# afstandbediening_shematic.net
KiCad netlist of a schematic drawn in Altium Designer
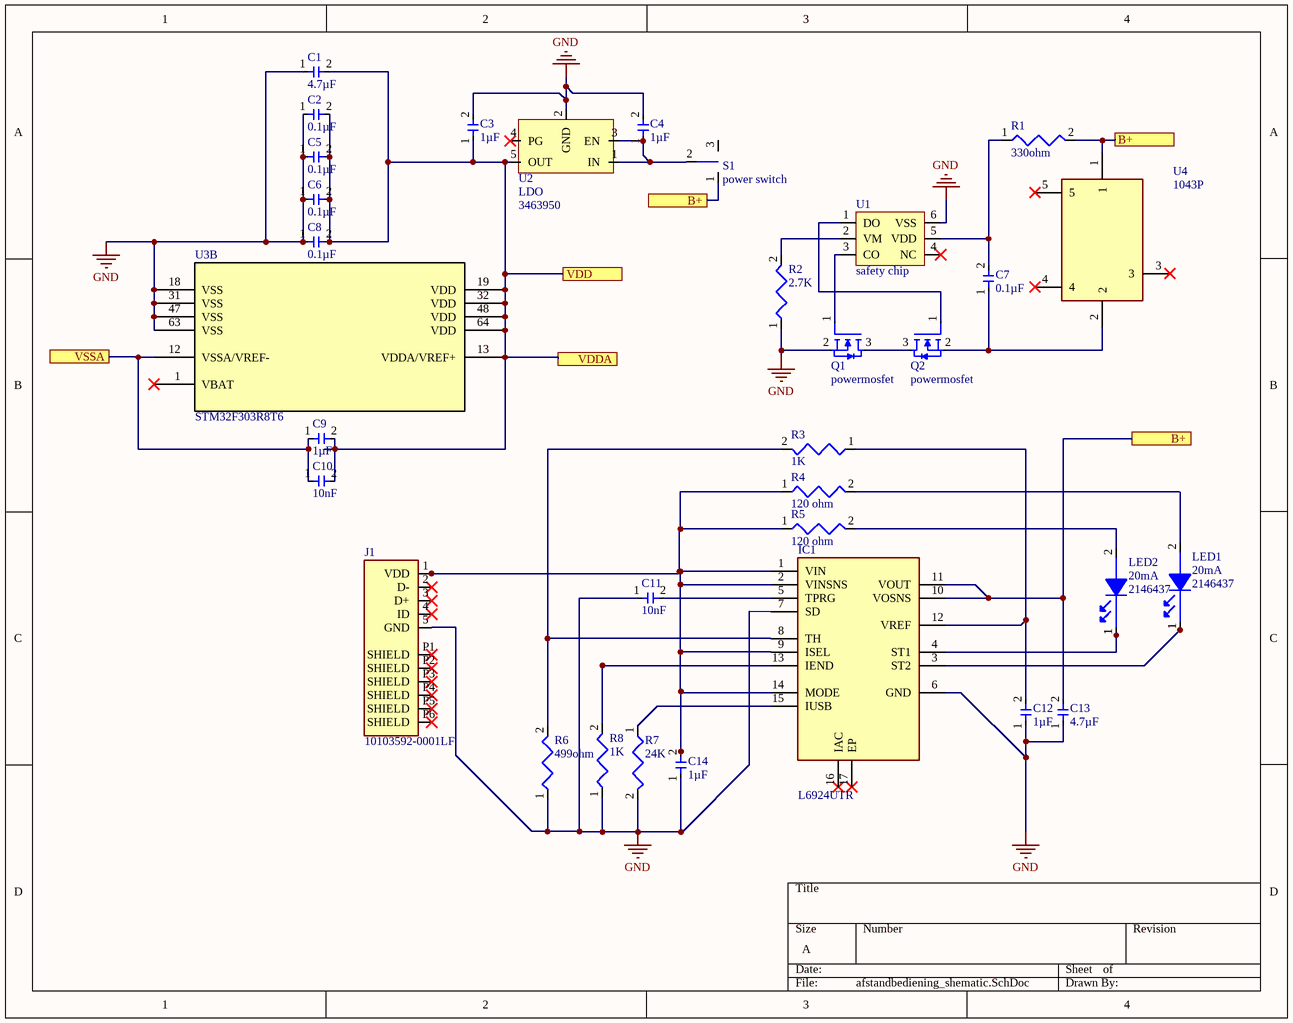
[diagram p0: afstandbediening_shematic.SchDoc]

(export (version "E")
  (design (tool "Eeschema 10.0.6"))
  (components
    (comp (ref "C1")
      (value "4.7µF")
      (footprint "0603")
      (fields
        (field (name "MANUFACTURER") "Kyocera AVX")
        (field (name "MANUFACTURER PART NUMBER") "0603ZD475KAT2A")
        (field (name "TOLERANCE") "10%")
      )
      (libsource (lib "afstandsbediening_library") (part "0603ZD475KAT2A"))
    )
    (comp (ref "C2")
      (value "0.1µF")
      (footprint "0603")
      (description "Cap Ceramic 0.1uF 16V X7R 10% SMD 0603 125C Paper T/R")
      (fields
        (field (name "MANUFACTURER") "Kyocera AVX")
        (field (name "MANUFACTURER PART NUMBER") "0603YC104KAT2A")
      )
      (libsource (lib "afstandsbediening_library") (part "0603YC104KAT2A"))
    )
    (comp (ref "C3")
      (value "1µF")
      (footprint "0603")
      (fields
        (field (name "MANUFACTURER") "Kyocera AVX")
        (field (name "MANUFACTURER PART NUMBER") "0603YD105KAT2A")
        (field (name "TOLERANCE") "10%")
      )
      (libsource (lib "afstandsbediening_library") (part "0603YD105KAT2A"))
    )
    (comp (ref "C4")
      (value "1µF")
      (footprint "0603")
      (fields
        (field (name "MANUFACTURER") "Kyocera AVX")
        (field (name "MANUFACTURER PART NUMBER") "0603YD105KAT2A")
        (field (name "TOLERANCE") "10%")
      )
      (libsource (lib "afstandsbediening_library") (part "0603YD105KAT2A"))
    )
    (comp (ref "C5")
      (value "0.1µF")
      (footprint "0603")
      (description "Cap Ceramic 0.1uF 16V X7R 10% SMD 0603 125C Paper T/R")
      (fields
        (field (name "MANUFACTURER") "Kyocera AVX")
        (field (name "MANUFACTURER PART NUMBER") "0603YC104KAT2A")
      )
      (libsource (lib "afstandsbediening_library") (part "0603YC104KAT2A"))
    )
    (comp (ref "C6")
      (value "0.1µF")
      (footprint "0603")
      (description "Cap Ceramic 0.1uF 16V X7R 10% SMD 0603 125C Paper T/R")
      (fields
        (field (name "MANUFACTURER") "Kyocera AVX")
        (field (name "MANUFACTURER PART NUMBER") "0603YC104KAT2A")
      )
      (libsource (lib "afstandsbediening_library") (part "0603YC104KAT2A"))
    )
    (comp (ref "C7")
      (value "0.1µF")
      (footprint "0603")
      (description "Cap Ceramic 0.1uF 16V X7R 10% SMD 0603 125C Paper T/R")
      (fields
        (field (name "MANUFACTURER") "Kyocera AVX")
        (field (name "MANUFACTURER PART NUMBER") "0603YC104KAT2A")
      )
      (libsource (lib "afstandsbediening_library") (part "0603YC104KAT2A"))
    )
    (comp (ref "C8")
      (value "0.1µF")
      (footprint "0603")
      (description "Cap Ceramic 0.1uF 16V X7R 10% SMD 0603 125C Paper T/R")
      (fields
        (field (name "MANUFACTURER") "Kyocera AVX")
        (field (name "MANUFACTURER PART NUMBER") "0603YC104KAT2A")
      )
      (libsource (lib "afstandsbediening_library") (part "0603YC104KAT2A"))
    )
    (comp (ref "C9")
      (value "1µF")
      (footprint "0603")
      (fields
        (field (name "MANUFACTURER") "Kyocera AVX")
        (field (name "MANUFACTURER PART NUMBER") "0603YD105KAT2A")
        (field (name "TOLERANCE") "10%")
      )
      (libsource (lib "afstandsbediening_library") (part "0603YD105KAT2A"))
    )
    (comp (ref "C10")
      (value "10nF")
      (footprint "0603")
      (fields
        (field (name "MANUFACTURER") "Kyocera AVX")
        (field (name "MANUFACTURER PART NUMBER") "0603YC103KAT2A")
        (field (name "TOLERANCE") "10%")
      )
      (libsource (lib "afstandsbediening_library") (part "0603YC103KAT2A"))
    )
    (comp (ref "C11")
      (value "10nF")
      (footprint "0603")
      (fields
        (field (name "MANUFACTURER") "Kyocera AVX")
        (field (name "MANUFACTURER PART NUMBER") "0603YC103KAT2A")
        (field (name "TOLERANCE") "10%")
      )
      (libsource (lib "afstandsbediening_library") (part "0603YC103KAT2A"))
    )
    (comp (ref "C12")
      (value "1µF")
      (footprint "0603")
      (fields
        (field (name "MANUFACTURER") "Kyocera AVX")
        (field (name "MANUFACTURER PART NUMBER") "0603YD105KAT2A")
        (field (name "TOLERANCE") "10%")
      )
      (libsource (lib "afstandsbediening_library") (part "0603YD105KAT2A"))
    )
    (comp (ref "C13")
      (value "4.7µF")
      (footprint "0603")
      (fields
        (field (name "MANUFACTURER") "Kyocera AVX")
        (field (name "MANUFACTURER PART NUMBER") "0603ZD475KAT2A")
        (field (name "TOLERANCE") "10%")
      )
      (libsource (lib "afstandsbediening_library") (part "0603ZD475KAT2A"))
    )
    (comp (ref "C14")
      (value "1µF")
      (footprint "0603")
      (fields
        (field (name "MANUFACTURER") "Kyocera AVX")
        (field (name "MANUFACTURER PART NUMBER") "0603YD105KAT2A")
        (field (name "TOLERANCE") "10%")
      )
      (libsource (lib "afstandsbediening_library") (part "0603YD105KAT2A"))
    )
    (comp (ref "IC1")
      (value "L6924UTR")
      (footprint "SamacSys:QFN50P300X300X100-17N-D")
      (description "Integrated Circuit")
      (fields (field (name "MOUSER2 PART NUMBER") "511-L6924UTR"))
      (libsource (lib "SamacSys") (part "L6924UTR"))
    )
    (comp (ref "J1")
      (value "10103592-0001LF")
      (footprint "AMPHENOL_10103592-0001LF")
      (description "USB - micro B USB 2.0 Receptacle Connector 5 Position Surface Mount, Right Angle; Through Hole")
      (fields (field (name "MF") "Amphenol ICC"))
      (libsource (lib "SamacSys") (part "10103592-0001LF"))
    )
    (comp (ref "LED1")
      (value "20mA")
      (footprint "KP-1608QBC-D")
      (description "LED Uni-Color Blue 468nm 2-Pin Chip LED T/R")
      (fields
        (field (name "MANUFACTURER") "Kingbright")
        (field (name "MANUFACTURER PART NUMBER") "KP-1608QBC-D")
        (field (name "SUPPLIER PART NUMBER 1") "2146437")
      )
      (libsource (lib "afstandsbediening_library") (part "KP-1608QBC-D"))
    )
    (comp (ref "LED2")
      (value "20mA")
      (footprint "KP-1608QBC-D")
      (description "LED Uni-Color Blue 468nm 2-Pin Chip LED T/R")
      (fields
        (field (name "MANUFACTURER") "Kingbright")
        (field (name "MANUFACTURER PART NUMBER") "KP-1608QBC-D")
        (field (name "SUPPLIER PART NUMBER 1") "2146437")
      )
      (libsource (lib "afstandsbediening_library") (part "KP-1608QBC-D"))
    )
    (comp (ref "Q1")
      (value "powermosfet")
      (footprint "SI2336DS-T1-GE3 - duplicate")
      (description "MOSFET N-CH 30V 5.2A SOT-23")
      (fields
        (field (name "MANUFACTURER") "Vishay Siliconix")
        (field (name "MANUFACTURER PART NUMBER") "SI2336DS-T1-GE3")
      )
      (libsource (lib "afstandsbediening_library") (part "SI2336DS-T1-GE3"))
    )
    (comp (ref "Q2")
      (value "powermosfet")
      (footprint "SI2336DS-T1-GE3 - duplicate")
      (description "MOSFET N-CH 30V 5.2A SOT-23")
      (fields
        (field (name "MANUFACTURER") "Vishay Siliconix")
        (field (name "MANUFACTURER PART NUMBER") "SI2336DS-T1-GE3")
      )
      (libsource (lib "afstandsbediening_library") (part "SI2336DS-T1-GE3"))
    )
    (comp (ref "R1")
      (value "330ohm")
      (footprint "MCWR08 - duplicate")
      (fields
        (field (name "MANUFACTURER") "Multicomp")
        (field (name "MANUFACTURER PART NUMBER") "MCWR08X3300FTL")
        (field (name "TOLERANCE") "1%")
      )
      (libsource (lib "afstandsbediening_library") (part "MCWR08X3300FTL"))
    )
    (comp (ref "R2")
      (value "2.7K")
      (footprint "CRCW0603")
      (description "SMD Resistor, Thick film 2.7 kOhm,  ±  1 %, 0603, CRCW06032K70FKEA, Vishay")
      (fields
        (field (name "MANUFACTURER") "Vishay")
        (field (name "MANUFACTURER PART NUMBER") "CRCW06032K70FKEA")
      )
      (libsource (lib "afstandsbediening_library") (part "CRCW06032K70FKEA"))
    )
    (comp (ref "R3")
      (value "1K")
      (footprint "CRCW0603")
      (fields
        (field (name "MANUFACTURER") "Vishay Dale")
        (field (name "MANUFACTURER PART NUMBER") "CRCW06031K00JNEA")
        (field (name "TOLERANCE") "5%")
      )
      (libsource (lib "afstandsbediening_library") (part "CRCW06031K00JNEA"))
    )
    (comp (ref "R4")
      (value "120 ohm")
      (footprint "CRCW0603")
      (description "Res Thick Film 0603 120 Ohm 1% 1/10W ±100ppm/°C Molded SMD Paper T/R")
      (fields
        (field (name "MANUFACTURER") "Vishay")
        (field (name "MANUFACTURER PART NUMBER") "CRCW0603120RFKEA")
      )
      (libsource (lib "afstandsbediening_library") (part "CRCW0603120RFKEA"))
    )
    (comp (ref "R5")
      (value "120 ohm")
      (footprint "CRCW0603")
      (description "Res Thick Film 0603 120 Ohm 1% 1/10W ±100ppm/°C Molded SMD Paper T/R")
      (fields
        (field (name "MANUFACTURER") "Vishay")
        (field (name "MANUFACTURER PART NUMBER") "CRCW0603120RFKEA")
      )
      (libsource (lib "afstandsbediening_library") (part "CRCW0603120RFKEA"))
    )
    (comp (ref "R6")
      (value "499ohm")
      (footprint "MCWR06")
      (description "Res, 499R, 1%, 0.1W, 0603, Thick Film")
      (fields
        (field (name "MANUFACTURER") "Multicomp")
        (field (name "MANUFACTURER PART NUMBER") "MCWR06X4990FTL")
      )
      (libsource (lib "afstandsbediening_library") (part "MCWR06X4990FTL"))
    )
    (comp (ref "R7")
      (value "24K")
      (footprint "MCWR06")
      (description "MULTICOMP - MCWR06X2402FTL - RES, 24K, 1%, 0.1W, THICK FILM")
      (fields
        (field (name "MANUFACTURER") "Multicomp")
        (field (name "MANUFACTURER PART NUMBER") "MCWR06X2402FTL")
      )
      (libsource (lib "afstandsbediening_library") (part "MCWR06X2402FTL"))
    )
    (comp (ref "R8")
      (value "1K")
      (footprint "CRCW0603")
      (fields
        (field (name "MANUFACTURER") "Vishay Dale")
        (field (name "MANUFACTURER PART NUMBER") "CRCW06031K00JNEA")
        (field (name "TOLERANCE") "5%")
      )
      (libsource (lib "afstandsbediening_library") (part "CRCW06031K00JNEA"))
    )
    (comp (ref "S1")
      (value "power switch")
      (footprint "T101MH9ABE")
      (description "SWITCH TOGGLE SPDT 0.4VA 20V")
      (fields (field (name "MANUFACTURER") "ITT C&K") (field (name "MANUFACTURER PART NUMBER") "T101MH9ABE"))
      (libsource (lib "afstandsbediening_library") (part "T101MH9ABE"))
    )
    (comp (ref "U1")
      (value "safety chip")
      (footprint "AP9101CK6-AETRG1")
      (description "IC BATT PROT LI-ION 1-CELL SOT26")
      (fields
        (field (name "MANUFACTURER") "Diodes")
        (field (name "MANUFACTURER PART NUMBER") "AP9101CK6-AETRG1")
      )
      (libsource (lib "afstandsbediening_library") (part "AP9101CK6-AETRG1"))
    )
    (comp (ref "U2")
      (value "LDO")
      (footprint "NCP164C")
      (description "MAX 5V, MIN 1.6V OUTPUT 3V")
      (fields
        (field (name "MANUFACTURER") "ON Semiconductor")
        (field (name "MANUFACTURER PART NUMBER") "NCP164CSN300T1G")
        (field (name "SUPPLIER PART NUMBER 1") "3463950")
      )
      (libsource (lib "afstandsbediening_library") (part "NCP164CSN300T1G"))
    )
    (comp (ref "U3")
      (value "STM32F303R8T6")
      (footprint "LQFP64-10x10mm")
      (description "No Description Available")
      (fields (field (name "COPYRIGHT") "Copyright (C) 2018 Accelerated Designs. All rights reserved"))
      (libsource (lib "2021-02-22_19-54-40") (part "STM32F303R8T6"))
    )
    (comp (ref "U4")
      (value "1043P")
      (footprint "SamacSys:1043P")
      (description "Undefined or Miscellaneous")
      (libsource (lib "SamacSys") (part "1043P"))
    )
  )
  (nets
    (net (code "1") (name "/B+") (class "Default")
      (node (ref "C13") (pin "2") (pinfunction "18_2") (pintype "passive"))
      (node (ref "IC1") (pin "10") (pinfunction "VOSNS_10") (pintype "passive"))
      (node (ref "IC1") (pin "11") (pinfunction "VOUT_11") (pintype "passive"))
      (node (ref "R1") (pin "2") (pinfunction "2_2") (pintype "passive"))
      (node (ref "S1") (pin "1") (pinfunction "1_1") (pintype "passive"))
      (node (ref "U4") (pin "1") (pinfunction "1_1") (pintype "passive"))
    )
    (net (code "2") (name "/VDD") (class "Default")
      (node (ref "C1") (pin "2") (pinfunction "18_2") (pintype "passive"))
      (node (ref "C10") (pin "2") (pinfunction "18_2") (pintype "passive"))
      (node (ref "C2") (pin "2") (pinfunction "18_2") (pintype "passive"))
      (node (ref "C3") (pin "1") (pinfunction "1_1") (pintype "passive"))
      (node (ref "C5") (pin "2") (pinfunction "18_2") (pintype "passive"))
      (node (ref "C6") (pin "2") (pinfunction "18_2") (pintype "passive"))
      (node (ref "C8") (pin "2") (pinfunction "18_2") (pintype "passive"))
      (node (ref "C9") (pin "2") (pinfunction "18_2") (pintype "passive"))
      (node (ref "U2") (pin "5") (pinfunction "OUT_5") (pintype "passive"))
      (node (ref "U3") (pin "13") (pinfunction "VDDA/VREF+_13") (pintype "power_in"))
      (node (ref "U3") (pin "19") (pinfunction "VDD_19") (pintype "power_in"))
      (node (ref "U3") (pin "32") (pinfunction "VDD_32") (pintype "power_in"))
      (node (ref "U3") (pin "48") (pinfunction "VDD_48") (pintype "power_in"))
      (node (ref "U3") (pin "64") (pinfunction "VDD_64") (pintype "power_in"))
    )
    (net (code "3") (name "/VSSA") (class "Default")
      (node (ref "C10") (pin "1") (pinfunction "1_1") (pintype "passive"))
      (node (ref "C9") (pin "1") (pinfunction "1_1") (pintype "passive"))
      (node (ref "U3") (pin "12") (pinfunction "VSSA/VREF-_12") (pintype "power_in"))
    )
    (net (code "4") (name "GND") (class "Default")
      (node (ref "C1") (pin "1") (pinfunction "1_1") (pintype "passive"))
      (node (ref "C11") (pin "1") (pinfunction "1_1") (pintype "passive"))
      (node (ref "C12") (pin "1") (pinfunction "1_1") (pintype "passive"))
      (node (ref "C13") (pin "1") (pinfunction "1_1") (pintype "passive"))
      (node (ref "C14") (pin "1") (pinfunction "1_1") (pintype "passive"))
      (node (ref "C2") (pin "1") (pinfunction "1_1") (pintype "passive"))
      (node (ref "C3") (pin "2") (pinfunction "18_2") (pintype "passive"))
      (node (ref "C4") (pin "2") (pinfunction "18_2") (pintype "passive"))
      (node (ref "C5") (pin "1") (pinfunction "1_1") (pintype "passive"))
      (node (ref "C6") (pin "1") (pinfunction "1_1") (pintype "passive"))
      (node (ref "C8") (pin "1") (pinfunction "1_1") (pintype "passive"))
      (node (ref "IC1") (pin "6") (pinfunction "GND_6") (pintype "passive"))
      (node (ref "IC1") (pin "7") (pinfunction "SD_7") (pintype "passive"))
      (node (ref "J1") (pin "5") (pinfunction "GND_5") (pintype "power_in"))
      (node (ref "Q1") (pin "2") (pinfunction "S_2") (pintype "passive"))
      (node (ref "R2") (pin "1") (pinfunction "1_1") (pintype "passive"))
      (node (ref "R6") (pin "1") (pinfunction "1_1") (pintype "passive"))
      (node (ref "R7") (pin "2") (pinfunction "2_2") (pintype "passive"))
      (node (ref "R8") (pin "1") (pinfunction "1_1") (pintype "passive"))
      (node (ref "U1") (pin "6") (pinfunction "VSS_6") (pintype "passive"))
      (node (ref "U2") (pin "2") (pinfunction "GND_2") (pintype "passive"))
      (node (ref "U3") (pin "18") (pinfunction "VSS_18") (pintype "power_in"))
      (node (ref "U3") (pin "31") (pinfunction "VSS_31") (pintype "power_in"))
      (node (ref "U3") (pin "47") (pinfunction "VSS_47") (pintype "power_in"))
      (node (ref "U3") (pin "63") (pinfunction "VSS_63") (pintype "power_in"))
    )
    (net (code "5") (name "Net-(C7-18)") (class "Default")
      (node (ref "C7") (pin "2") (pinfunction "18_2") (pintype "passive"))
      (node (ref "R1") (pin "1") (pinfunction "1_1") (pintype "passive"))
      (node (ref "U1") (pin "5") (pinfunction "VDD_5") (pintype "passive"))
    )
    (net (code "6") (name "Net-(C11-18)") (class "Default")
      (node (ref "C11") (pin "2") (pinfunction "18_2") (pintype "passive"))
      (node (ref "IC1") (pin "5") (pinfunction "TPRG_5") (pintype "passive"))
    )
    (net (code "7") (name "Net-(C12-18)") (class "Default")
      (node (ref "C12") (pin "2") (pinfunction "18_2") (pintype "passive"))
      (node (ref "IC1") (pin "12") (pinfunction "VREF_12") (pintype "passive"))
      (node (ref "R3") (pin "1") (pinfunction "1_1") (pintype "passive"))
    )
    (net (code "8") (name "Net-(C14-18)") (class "Default")
      (node (ref "C14") (pin "2") (pinfunction "18_2") (pintype "passive"))
      (node (ref "IC1") (pin "1") (pinfunction "VIN_1") (pintype "passive"))
      (node (ref "IC1") (pin "14") (pinfunction "MODE_14") (pintype "passive"))
      (node (ref "IC1") (pin "2") (pinfunction "VINSNS_2") (pintype "passive"))
      (node (ref "IC1") (pin "9") (pinfunction "ISEL_9") (pintype "passive"))
      (node (ref "J1") (pin "1") (pinfunction "VDD_1") (pintype "power_in"))
      (node (ref "R4") (pin "1") (pinfunction "1_1") (pintype "passive"))
      (node (ref "R5") (pin "1") (pinfunction "1_1") (pintype "passive"))
    )
    (net (code "9") (name "Net-(IC1-IEND)") (class "Default")
      (node (ref "IC1") (pin "13") (pinfunction "IEND_13") (pintype "passive"))
      (node (ref "R8") (pin "2") (pinfunction "2_2") (pintype "passive"))
    )
    (net (code "10") (name "Net-(IC1-IUSB)") (class "Default")
      (node (ref "IC1") (pin "15") (pinfunction "IUSB_15") (pintype "passive"))
      (node (ref "R7") (pin "1") (pinfunction "1_1") (pintype "passive"))
    )
    (net (code "11") (name "Net-(IC1-ST1)") (class "Default")
      (node (ref "IC1") (pin "4") (pinfunction "ST1_4") (pintype "passive"))
      (node (ref "LED2") (pin "1") (pinfunction "1_1") (pintype "passive"))
    )
    (net (code "12") (name "Net-(IC1-ST2)") (class "Default")
      (node (ref "IC1") (pin "3") (pinfunction "ST2_3") (pintype "passive"))
      (node (ref "LED1") (pin "1") (pinfunction "1_1") (pintype "passive"))
    )
    (net (code "13") (name "Net-(IC1-TH)") (class "Default")
      (node (ref "IC1") (pin "8") (pinfunction "TH_8") (pintype "passive"))
      (node (ref "R3") (pin "2") (pinfunction "2_2") (pintype "passive"))
      (node (ref "R6") (pin "2") (pinfunction "2_2") (pintype "passive"))
    )
    (net (code "14") (name "Net-(LED1-Pad2)") (class "Default")
      (node (ref "LED1") (pin "2") (pinfunction "2_2") (pintype "passive"))
      (node (ref "R4") (pin "2") (pinfunction "2_2") (pintype "passive"))
    )
    (net (code "15") (name "Net-(LED2-Pad2)") (class "Default")
      (node (ref "LED2") (pin "2") (pinfunction "2_2") (pintype "passive"))
      (node (ref "R5") (pin "2") (pinfunction "2_2") (pintype "passive"))
    )
    (net (code "16") (name "Net-(Q1-D)") (class "Default")
      (node (ref "Q1") (pin "3") (pinfunction "D_3") (pintype "passive"))
      (node (ref "Q2") (pin "3") (pinfunction "D_3") (pintype "passive"))
    )
    (net (code "17") (name "Net-(Q1-G)") (class "Default")
      (node (ref "Q1") (pin "1") (pinfunction "G_1") (pintype "passive"))
      (node (ref "U1") (pin "3") (pinfunction "CO_3") (pintype "passive"))
    )
    (net (code "18") (name "Net-(Q2-G)") (class "Default")
      (node (ref "Q2") (pin "1") (pinfunction "G_1") (pintype "passive"))
      (node (ref "U1") (pin "1") (pinfunction "DO_1") (pintype "passive"))
    )
    (net (code "19") (name "Net-(Q2-S)") (class "Default")
      (node (ref "C7") (pin "1") (pinfunction "1_1") (pintype "passive"))
      (node (ref "Q2") (pin "2") (pinfunction "S_2") (pintype "passive"))
      (node (ref "U4") (pin "2") (pinfunction "2_2") (pintype "passive"))
    )
    (net (code "20") (name "Net-(U1-VM)") (class "Default")
      (node (ref "R2") (pin "2") (pinfunction "2_2") (pintype "passive"))
      (node (ref "U1") (pin "2") (pinfunction "VM_2") (pintype "passive"))
    )
    (net (code "21") (name "Net-(U2-EN)") (class "Default")
      (node (ref "C4") (pin "1") (pinfunction "1_1") (pintype "passive"))
      (node (ref "S1") (pin "2") (pinfunction "2_2") (pintype "passive"))
      (node (ref "U2") (pin "1") (pinfunction "IN_1") (pintype "passive"))
      (node (ref "U2") (pin "3") (pinfunction "EN_3") (pintype "passive"))
    )
    (net (code "22") (name "unconnected-(IC1-EP-Pad17)") (class "Default")
      (node (ref "IC1") (pin "17") (pinfunction "EP_17") (pintype "passive+no_connect"))
    )
    (net (code "23") (name "unconnected-(IC1-IAC-Pad16)") (class "Default")
      (node (ref "IC1") (pin "16") (pinfunction "IAC_16") (pintype "passive+no_connect"))
    )
    (net (code "24") (name "unconnected-(J1-D+-Pad3)") (class "Default")
      (node (ref "J1") (pin "3") (pinfunction "D+_3") (pintype "bidirectional+no_connect"))
    )
    (net (code "25") (name "unconnected-(J1-D--Pad2)") (class "Default")
      (node (ref "J1") (pin "2") (pinfunction "D-_2") (pintype "bidirectional+no_connect"))
    )
    (net (code "26") (name "unconnected-(J1-ID-Pad4)") (class "Default")
      (node (ref "J1") (pin "4") (pinfunction "ID_4") (pintype "bidirectional+no_connect"))
    )
    (net (code "27") (name "unconnected-(J1-SHIELD-PadP1)") (class "Default")
      (node (ref "J1") (pin "P1") (pinfunction "SHIELD_P1") (pintype "power_in+no_connect"))
    )
    (net (code "28") (name "unconnected-(J1-SHIELD-PadP2)") (class "Default")
      (node (ref "J1") (pin "P2") (pinfunction "SHIELD_P2") (pintype "power_in+no_connect"))
    )
    (net (code "29") (name "unconnected-(J1-SHIELD-PadP3)") (class "Default")
      (node (ref "J1") (pin "P3") (pinfunction "SHIELD_P3") (pintype "power_in+no_connect"))
    )
    (net (code "30") (name "unconnected-(J1-SHIELD-PadP4)") (class "Default")
      (node (ref "J1") (pin "P4") (pinfunction "SHIELD_P4") (pintype "power_in+no_connect"))
    )
    (net (code "31") (name "unconnected-(J1-SHIELD-PadP5)") (class "Default")
      (node (ref "J1") (pin "P5") (pinfunction "SHIELD_P5") (pintype "power_in+no_connect"))
    )
    (net (code "32") (name "unconnected-(J1-SHIELD-PadP6)") (class "Default")
      (node (ref "J1") (pin "P6") (pinfunction "SHIELD_P6") (pintype "power_in+no_connect"))
    )
    (net (code "33") (name "unconnected-(S1-Pad3)") (class "Default")
      (node (ref "S1") (pin "3") (pinfunction "3_3") (pintype "passive"))
    )
    (net (code "34") (name "unconnected-(U1-NC-Pad4)") (class "Default")
      (node (ref "U1") (pin "4") (pinfunction "NC_4") (pintype "passive+no_connect"))
    )
    (net (code "35") (name "unconnected-(U2-PG-Pad4)") (class "Default")
      (node (ref "U2") (pin "4") (pinfunction "PG_4") (pintype "passive+no_connect"))
    )
    (net (code "36") (name "unconnected-(U3B-VBAT-Pad1)") (class "Default")
      (node (ref "U3") (pin "1") (pinfunction "VBAT_1") (pintype "power_in+no_connect"))
    )
    (net (code "37") (name "unconnected-(U4-Pad3)") (class "Default")
      (node (ref "U4") (pin "3") (pinfunction "3_3") (pintype "passive+no_connect"))
    )
    (net (code "38") (name "unconnected-(U4-Pad4)") (class "Default")
      (node (ref "U4") (pin "4") (pinfunction "4_4") (pintype "passive+no_connect"))
    )
    (net (code "39") (name "unconnected-(U4-Pad5)") (class "Default")
      (node (ref "U4") (pin "5") (pinfunction "5_5") (pintype "passive+no_connect"))
    )
  )
)
